# Street_Fighter_v1_2.net
KiCad netlist of a schematic drawn in EAGLE
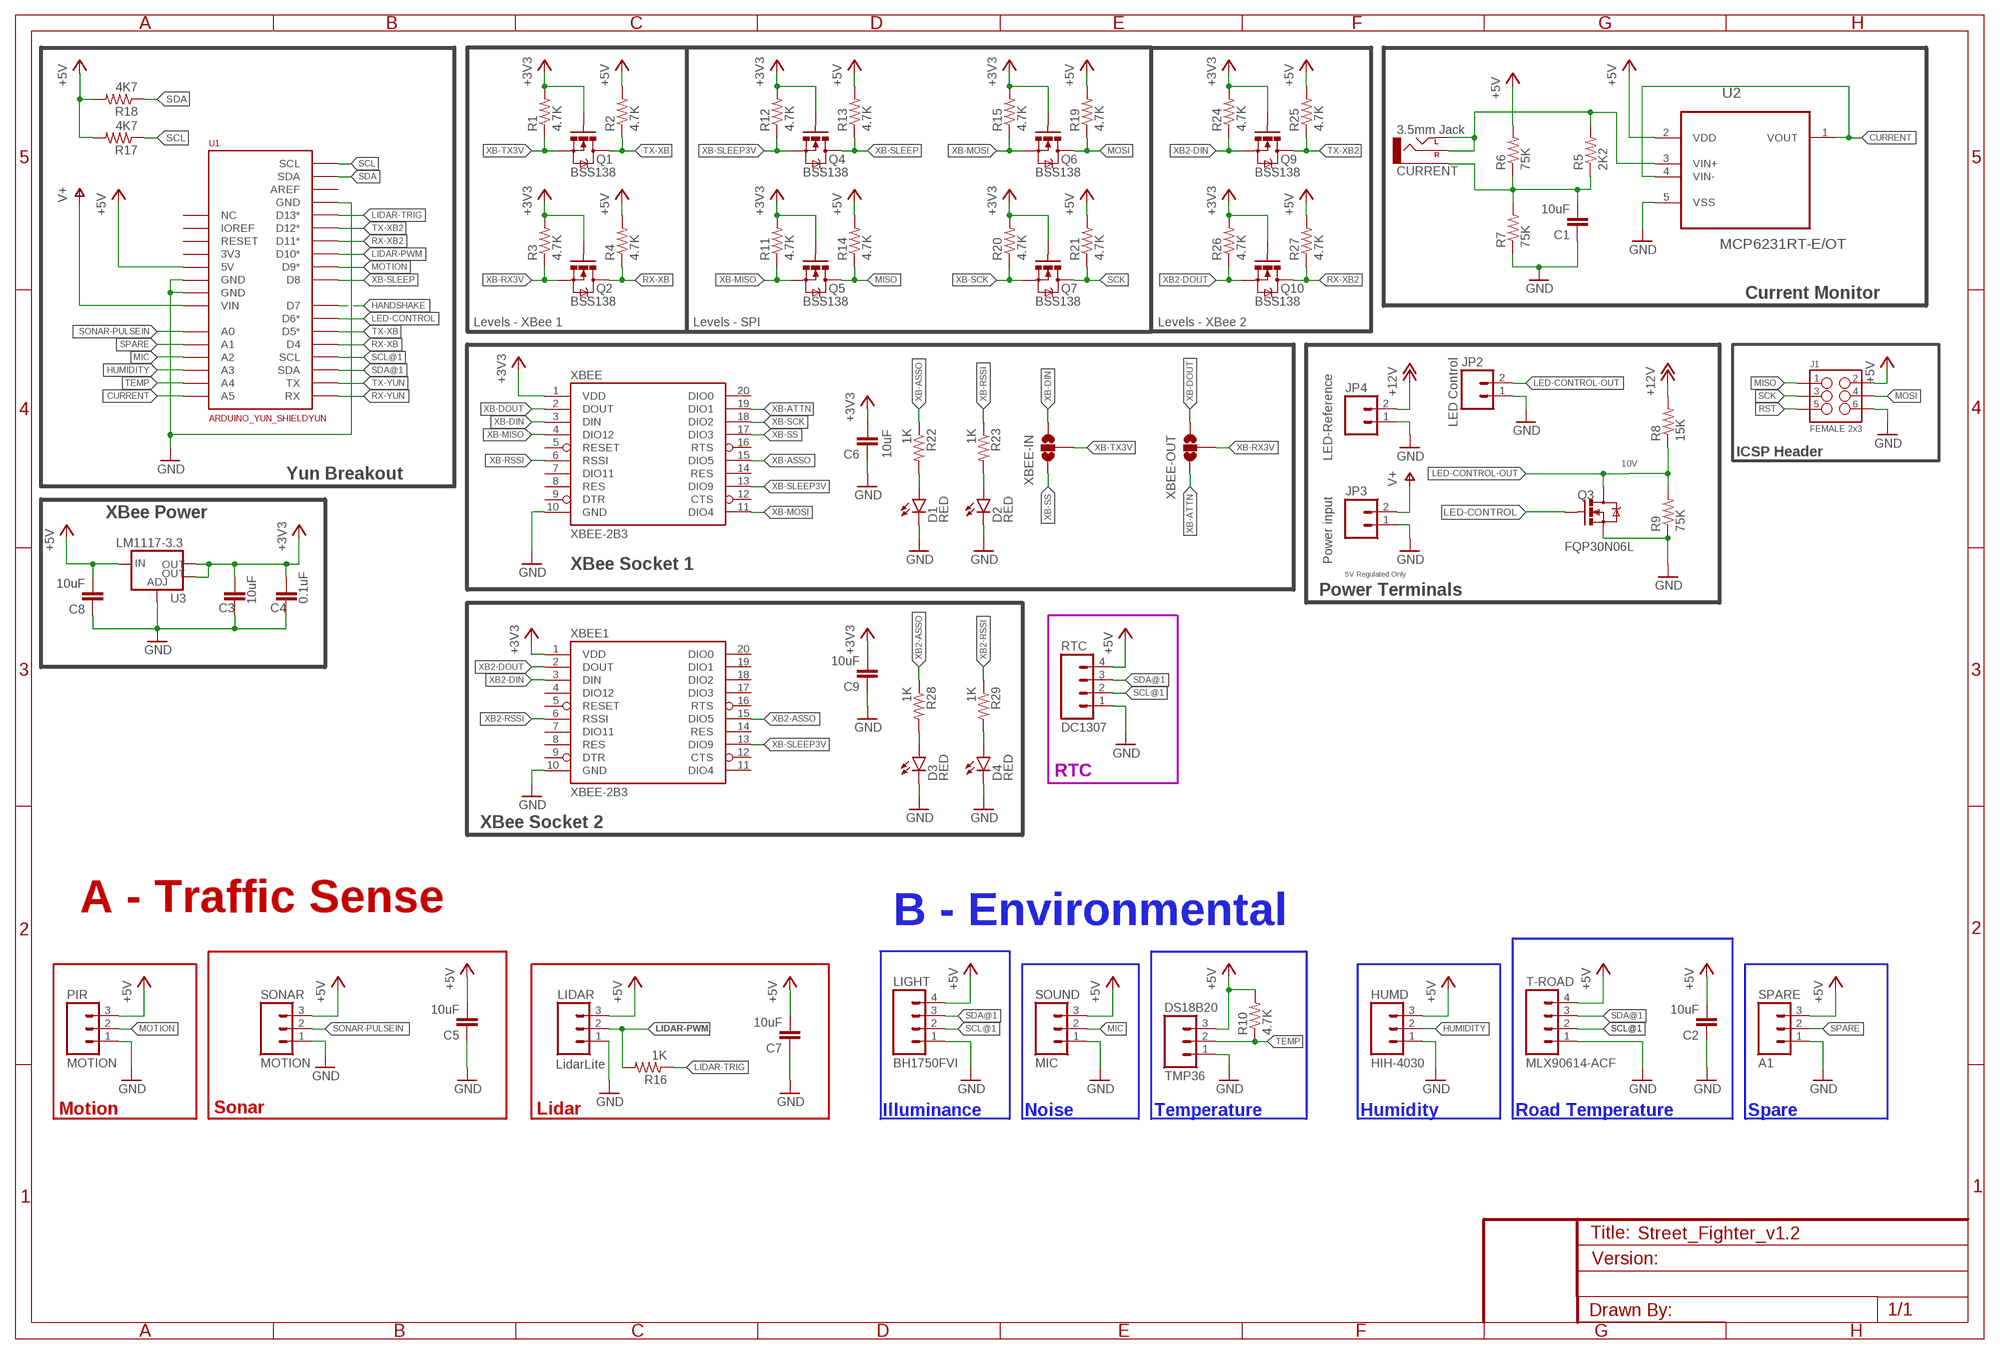
[diagram p0: schematic, sheet 1]

(export (version "E")
  (design (tool "Eeschema 10.0.6"))
  (components
    (comp (ref "C1")
      (value "10uF")
      (footprint "eagle-import:1206")
      (libsource (lib "eagle-import") (part "10UF-6.3V-20%(1206)"))
    )
    (comp (ref "C2")
      (value "10uF")
      (footprint "eagle-import:1206")
      (libsource (lib "eagle-import") (part "10UF-6.3V-20%(1206)"))
    )
    (comp (ref "C3")
      (value "10uF")
      (footprint "eagle-import:1206")
      (libsource (lib "eagle-import") (part "10UF-6.3V-20%(1206)"))
    )
    (comp (ref "C4")
      (value "0.1uF")
      (footprint "eagle-import:1206")
      (libsource (lib "eagle-import") (part "10UF-6.3V-20%(1206)"))
    )
    (comp (ref "C5")
      (value "10uF")
      (footprint "eagle-import:1206")
      (libsource (lib "eagle-import") (part "10UF-6.3V-20%(1206)"))
    )
    (comp (ref "C6")
      (value "10uF")
      (footprint "eagle-import:1206")
      (libsource (lib "eagle-import") (part "10UF-6.3V-20%(1206)"))
    )
    (comp (ref "C7")
      (value "10uF")
      (footprint "eagle-import:1206")
      (libsource (lib "eagle-import") (part "10UF-6.3V-20%(1206)"))
    )
    (comp (ref "C8")
      (value "10uF")
      (footprint "eagle-import:1206")
      (libsource (lib "eagle-import") (part "10UF-6.3V-20%(1206)"))
    )
    (comp (ref "C9")
      (value "10uF")
      (footprint "eagle-import:1206")
      (libsource (lib "eagle-import") (part "10UF-6.3V-20%(1206)"))
    )
    (comp (ref "CURRENT")
      (value "3.5mm Jack")
      (footprint "eagle-import:AUDIO-JACK")
      (libsource (lib "eagle-import") (part "AUDIO-JACKPTH"))
    )
    (comp (ref "D1")
      (value "RED")
      (footprint "eagle-import:LED-1206")
      (libsource (lib "eagle-import") (part "LED-RED1206"))
    )
    (comp (ref "D2")
      (value "RED")
      (footprint "eagle-import:LED-1206")
      (libsource (lib "eagle-import") (part "LED-RED1206"))
    )
    (comp (ref "D3")
      (value "RED")
      (footprint "eagle-import:LED-1206")
      (libsource (lib "eagle-import") (part "LED-RED1206"))
    )
    (comp (ref "D4")
      (value "RED")
      (footprint "eagle-import:LED-1206")
      (libsource (lib "eagle-import") (part "LED-RED1206"))
    )
    (comp (ref "DS18B20")
      (value "TMP36")
      (footprint "eagle-import:1X03")
      (libsource (lib "eagle-import") (part "M03PTH"))
    )
    (comp (ref "HUMD")
      (value "HIH-4030")
      (footprint "eagle-import:1X03")
      (libsource (lib "eagle-import") (part "M03PTH"))
    )
    (comp (ref "J1")
      (value "FEMALE 2x3")
      (footprint "eagle-import:2X3")
      (libsource (lib "eagle-import") (part "M03X2FEMALE"))
    )
    (comp (ref "JP2")
      (value "LED Control")
      (footprint "eagle-import:1X02_LONGPADS")
      (libsource (lib "eagle-import") (part "M02PTH3"))
    )
    (comp (ref "JP3")
      (value "Power input")
      (footprint "eagle-import:1X02_LONGPADS")
      (libsource (lib "eagle-import") (part "M02PTH3"))
    )
    (comp (ref "JP4")
      (value "LED-Reference")
      (footprint "eagle-import:1X02_LONGPADS")
      (libsource (lib "eagle-import") (part "M02PTH3"))
    )
    (comp (ref "LIDAR")
      (value "LidarLite")
      (footprint "eagle-import:1X03")
      (libsource (lib "eagle-import") (part "M03PTH"))
    )
    (comp (ref "LIGHT")
      (value "BH1750FVI")
      (footprint "eagle-import:1X04")
      (libsource (lib "eagle-import") (part "M04PTH"))
    )
    (comp (ref "PIR")
      (value "MOTION")
      (footprint "eagle-import:1X03")
      (libsource (lib "eagle-import") (part "M03PTH"))
    )
    (comp (ref "Q1")
      (value "BSS138")
      (footprint "eagle-import:SOT23")
      (libsource (lib "eagle-import") (part "MOSFET-NCHANNELBSS123LT1G"))
    )
    (comp (ref "Q2")
      (value "BSS138")
      (footprint "eagle-import:SOT23")
      (libsource (lib "eagle-import") (part "MOSFET-NCHANNELBSS123LT1G"))
    )
    (comp (ref "Q3")
      (value "FQP30N06L")
      (footprint "eagle-import:TO220V")
      (libsource (lib "eagle-import") (part "MOSFET-NCHANNELFQP30N06L"))
    )
    (comp (ref "Q4")
      (value "BSS138")
      (footprint "eagle-import:SOT23")
      (libsource (lib "eagle-import") (part "MOSFET-NCHANNELBSS123LT1G"))
    )
    (comp (ref "Q5")
      (value "BSS138")
      (footprint "eagle-import:SOT23")
      (libsource (lib "eagle-import") (part "MOSFET-NCHANNELBSS123LT1G"))
    )
    (comp (ref "Q6")
      (value "BSS138")
      (footprint "eagle-import:SOT23")
      (libsource (lib "eagle-import") (part "MOSFET-NCHANNELBSS123LT1G"))
    )
    (comp (ref "Q7")
      (value "BSS138")
      (footprint "eagle-import:SOT23")
      (libsource (lib "eagle-import") (part "MOSFET-NCHANNELBSS123LT1G"))
    )
    (comp (ref "Q9")
      (value "BSS138")
      (footprint "eagle-import:SOT23")
      (libsource (lib "eagle-import") (part "MOSFET-NCHANNELBSS123LT1G"))
    )
    (comp (ref "Q10")
      (value "BSS138")
      (footprint "eagle-import:SOT23")
      (libsource (lib "eagle-import") (part "MOSFET-NCHANNELBSS123LT1G"))
    )
    (comp (ref "R1")
      (value "4.7K")
      (footprint "eagle-import:1206")
      (libsource (lib "eagle-import") (part "RESISTOR1206"))
    )
    (comp (ref "R2")
      (value "4.7K")
      (footprint "eagle-import:1206")
      (libsource (lib "eagle-import") (part "RESISTOR1206"))
    )
    (comp (ref "R3")
      (value "4.7K")
      (footprint "eagle-import:1206")
      (libsource (lib "eagle-import") (part "RESISTOR1206"))
    )
    (comp (ref "R4")
      (value "4.7K")
      (footprint "eagle-import:1206")
      (libsource (lib "eagle-import") (part "RESISTOR1206"))
    )
    (comp (ref "R5")
      (value "2K2")
      (footprint "eagle-import:1206")
      (libsource (lib "eagle-import") (part "RESISTOR1206"))
    )
    (comp (ref "R6")
      (value "75K")
      (footprint "eagle-import:1206")
      (libsource (lib "eagle-import") (part "RESISTOR1206"))
    )
    (comp (ref "R7")
      (value "75K")
      (footprint "eagle-import:1206")
      (libsource (lib "eagle-import") (part "RESISTOR1206"))
    )
    (comp (ref "R8")
      (value "15K")
      (footprint "eagle-import:1206")
      (libsource (lib "eagle-import") (part "RESISTOR1206"))
    )
    (comp (ref "R9")
      (value "75K")
      (footprint "eagle-import:1206")
      (libsource (lib "eagle-import") (part "RESISTOR1206"))
    )
    (comp (ref "R10")
      (value "4.7K")
      (footprint "eagle-import:1206")
      (libsource (lib "eagle-import") (part "RESISTOR1206"))
    )
    (comp (ref "R11")
      (value "4.7K")
      (footprint "eagle-import:1206")
      (libsource (lib "eagle-import") (part "RESISTOR1206"))
    )
    (comp (ref "R12")
      (value "4.7K")
      (footprint "eagle-import:1206")
      (libsource (lib "eagle-import") (part "RESISTOR1206"))
    )
    (comp (ref "R13")
      (value "4.7K")
      (footprint "eagle-import:1206")
      (libsource (lib "eagle-import") (part "RESISTOR1206"))
    )
    (comp (ref "R14")
      (value "4.7K")
      (footprint "eagle-import:1206")
      (libsource (lib "eagle-import") (part "RESISTOR1206"))
    )
    (comp (ref "R15")
      (value "4.7K")
      (footprint "eagle-import:1206")
      (libsource (lib "eagle-import") (part "RESISTOR1206"))
    )
    (comp (ref "R16")
      (value "1K")
      (footprint "eagle-import:1206")
      (libsource (lib "eagle-import") (part "RESISTOR1206"))
    )
    (comp (ref "R17")
      (value "4K7")
      (footprint "eagle-import:1206")
      (libsource (lib "eagle-import") (part "RESISTOR1206"))
    )
    (comp (ref "R18")
      (value "4K7")
      (footprint "eagle-import:1206")
      (libsource (lib "eagle-import") (part "RESISTOR1206"))
    )
    (comp (ref "R19")
      (value "4.7K")
      (footprint "eagle-import:1206")
      (libsource (lib "eagle-import") (part "RESISTOR1206"))
    )
    (comp (ref "R20")
      (value "4.7K")
      (footprint "eagle-import:1206")
      (libsource (lib "eagle-import") (part "RESISTOR1206"))
    )
    (comp (ref "R21")
      (value "4.7K")
      (footprint "eagle-import:1206")
      (libsource (lib "eagle-import") (part "RESISTOR1206"))
    )
    (comp (ref "R22")
      (value "1K")
      (footprint "eagle-import:1206")
      (libsource (lib "eagle-import") (part "RESISTOR1206"))
    )
    (comp (ref "R23")
      (value "1K")
      (footprint "eagle-import:1206")
      (libsource (lib "eagle-import") (part "RESISTOR1206"))
    )
    (comp (ref "R24")
      (value "4.7K")
      (footprint "eagle-import:1206")
      (libsource (lib "eagle-import") (part "RESISTOR1206"))
    )
    (comp (ref "R25")
      (value "4.7K")
      (footprint "eagle-import:1206")
      (libsource (lib "eagle-import") (part "RESISTOR1206"))
    )
    (comp (ref "R26")
      (value "4.7K")
      (footprint "eagle-import:1206")
      (libsource (lib "eagle-import") (part "RESISTOR1206"))
    )
    (comp (ref "R27")
      (value "4.7K")
      (footprint "eagle-import:1206")
      (libsource (lib "eagle-import") (part "RESISTOR1206"))
    )
    (comp (ref "R28")
      (value "1K")
      (footprint "eagle-import:1206")
      (libsource (lib "eagle-import") (part "RESISTOR1206"))
    )
    (comp (ref "R29")
      (value "1K")
      (footprint "eagle-import:1206")
      (libsource (lib "eagle-import") (part "RESISTOR1206"))
    )
    (comp (ref "RTC")
      (value "DC1307")
      (footprint "eagle-import:1X04")
      (libsource (lib "eagle-import") (part "M04PTH"))
    )
    (comp (ref "SONAR")
      (value "MOTION")
      (footprint "eagle-import:1X03")
      (libsource (lib "eagle-import") (part "M03PTH"))
    )
    (comp (ref "SOUND")
      (value "MIC")
      (footprint "eagle-import:1X03")
      (libsource (lib "eagle-import") (part "M03PTH"))
    )
    (comp (ref "SPARE")
      (value "A1")
      (footprint "eagle-import:1X03")
      (libsource (lib "eagle-import") (part "M03PTH"))
    )
    (comp (ref "T-ROAD")
      (value "MLX90614-ACF")
      (footprint "eagle-import:1X04")
      (libsource (lib "eagle-import") (part "M04PTH"))
    )
    (comp (ref "U1")
      (value "ARDUINO_YUN_SHIELDYUN")
      (footprint "eagle-import:DUEMILANOVE_VIAS")
      (libsource (lib "eagle-import") (part "ARDUINO_YUN_SHIELDYUN"))
    )
    (comp (ref "U2")
      (value "MCP6231RT-E/OT")
      (footprint "eagle-import:SOT95P270X145-5N")
      (libsource (lib "eagle-import") (part "MCP6231RT-E/OT"))
    )
    (comp (ref "U3")
      (value "LM1117-3.3")
      (footprint "eagle-import:SOT223")
      (libsource (lib "eagle-import") (part "V_REG_LM1117SOT223"))
    )
    (comp (ref "XBEE")
      (value "XBEE-2B3")
      (footprint "eagle-import:XBEE-SMD")
      (libsource (lib "eagle-import") (part "XBEE-2B3"))
    )
    (comp (ref "XBEE-IN")
      (value "SOLDERJUMPER_2WAYS")
      (footprint "eagle-import:SJ_3")
      (libsource (lib "eagle-import") (part "SOLDERJUMPER_2WAYS"))
    )
    (comp (ref "XBEE-OUT")
      (value "SOLDERJUMPER_2WAYS")
      (footprint "eagle-import:SJ_3")
      (libsource (lib "eagle-import") (part "SOLDERJUMPER_2WAYS"))
    )
    (comp (ref "XBEE1")
      (value "XBEE-2B3")
      (footprint "eagle-import:XBEE-SMD")
      (libsource (lib "eagle-import") (part "XBEE-2B3"))
    )
  )
  (nets
    (net (code "1") (name "+3V3") (class "Default")
      (node (ref "C3") (pin "2") (pinfunction "2_2") (pintype "passive"))
      (node (ref "C4") (pin "2") (pinfunction "2_2") (pintype "passive"))
      (node (ref "C6") (pin "2") (pinfunction "2_2") (pintype "passive"))
      (node (ref "C9") (pin "2") (pinfunction "2_2") (pintype "passive"))
      (node (ref "Q1") (pin "1") (pinfunction "G_1") (pintype "passive"))
      (node (ref "Q10") (pin "1") (pinfunction "G_1") (pintype "passive"))
      (node (ref "Q2") (pin "1") (pinfunction "G_1") (pintype "passive"))
      (node (ref "Q4") (pin "1") (pinfunction "G_1") (pintype "passive"))
      (node (ref "Q5") (pin "1") (pinfunction "G_1") (pintype "passive"))
      (node (ref "Q6") (pin "1") (pinfunction "G_1") (pintype "passive"))
      (node (ref "Q7") (pin "1") (pinfunction "G_1") (pintype "passive"))
      (node (ref "Q9") (pin "1") (pinfunction "G_1") (pintype "passive"))
      (node (ref "R1") (pin "2") (pinfunction "2_2") (pintype "passive"))
      (node (ref "R11") (pin "2") (pinfunction "2_2") (pintype "passive"))
      (node (ref "R12") (pin "2") (pinfunction "2_2") (pintype "passive"))
      (node (ref "R15") (pin "2") (pinfunction "2_2") (pintype "passive"))
      (node (ref "R20") (pin "2") (pinfunction "2_2") (pintype "passive"))
      (node (ref "R24") (pin "2") (pinfunction "2_2") (pintype "passive"))
      (node (ref "R26") (pin "2") (pinfunction "2_2") (pintype "passive"))
      (node (ref "R3") (pin "2") (pinfunction "2_2") (pintype "passive"))
      (node (ref "U3") (pin "2") (pinfunction "OUT_2") (pintype "output"))
      (node (ref "U3") (pin "4") (pinfunction "OUT_4") (pintype "output"))
      (node (ref "XBEE") (pin "1") (pinfunction "VDD_1") (pintype "power_in"))
      (node (ref "XBEE1") (pin "1") (pinfunction "VDD_1") (pintype "power_in"))
    )
    (net (code "2") (name "+5V") (class "Default")
      (node (ref "C2") (pin "2") (pinfunction "2_2") (pintype "passive"))
      (node (ref "C5") (pin "2") (pinfunction "2_2") (pintype "passive"))
      (node (ref "C7") (pin "2") (pinfunction "2_2") (pintype "passive"))
      (node (ref "C8") (pin "2") (pinfunction "2_2") (pintype "passive"))
      (node (ref "DS18B20") (pin "3") (pinfunction "3_3") (pintype "passive"))
      (node (ref "HUMD") (pin "3") (pinfunction "3_3") (pintype "passive"))
      (node (ref "J1") (pin "2") (pinfunction "2_2") (pintype "bidirectional"))
      (node (ref "LIDAR") (pin "3") (pinfunction "3_3") (pintype "passive"))
      (node (ref "LIGHT") (pin "4") (pinfunction "4_4") (pintype "passive"))
      (node (ref "PIR") (pin "3") (pinfunction "3_3") (pintype "passive"))
      (node (ref "R10") (pin "2") (pinfunction "2_2") (pintype "passive"))
      (node (ref "R13") (pin "2") (pinfunction "2_2") (pintype "passive"))
      (node (ref "R14") (pin "2") (pinfunction "2_2") (pintype "passive"))
      (node (ref "R17") (pin "2") (pinfunction "2_2") (pintype "passive"))
      (node (ref "R18") (pin "2") (pinfunction "2_2") (pintype "passive"))
      (node (ref "R19") (pin "2") (pinfunction "2_2") (pintype "passive"))
      (node (ref "R2") (pin "2") (pinfunction "2_2") (pintype "passive"))
      (node (ref "R21") (pin "2") (pinfunction "2_2") (pintype "passive"))
      (node (ref "R25") (pin "2") (pinfunction "2_2") (pintype "passive"))
      (node (ref "R27") (pin "2") (pinfunction "2_2") (pintype "passive"))
      (node (ref "R4") (pin "2") (pinfunction "2_2") (pintype "passive"))
      (node (ref "R6") (pin "2") (pinfunction "2_2") (pintype "passive"))
      (node (ref "RTC") (pin "4") (pinfunction "4_4") (pintype "passive"))
      (node (ref "SONAR") (pin "3") (pinfunction "3_3") (pintype "passive"))
      (node (ref "SOUND") (pin "3") (pinfunction "3_3") (pintype "passive"))
      (node (ref "SPARE") (pin "3") (pinfunction "3_3") (pintype "passive"))
      (node (ref "T-ROAD") (pin "4") (pinfunction "4_4") (pintype "passive"))
      (node (ref "U1") (pin "5V") (pinfunction "5V_5V") (pintype "power_in"))
      (node (ref "U2") (pin "2") (pinfunction "VDD_2") (pintype "power_in"))
      (node (ref "U3") (pin "3") (pinfunction "IN_3") (pintype "input"))
    )
    (net (code "3") (name "+12V") (class "Default")
      (node (ref "JP4") (pin "2") (pinfunction "2_2") (pintype "passive"))
      (node (ref "R8") (pin "2") (pinfunction "2_2") (pintype "passive"))
    )
    (net (code "4") (name "/3V3") (class "Default")
      (node (ref "U1") (pin "3V3") (pinfunction "3V3_3V3") (pintype "power_in"))
    )
    (net (code "5") (name "CURRENT") (class "Default")
      (node (ref "U1") (pin "A5") (pinfunction "A5_A5") (pintype "bidirectional"))
      (node (ref "U2") (pin "1") (pinfunction "VOUT_1") (pintype "output"))
      (node (ref "U2") (pin "4") (pinfunction "VIN-_4") (pintype "input"))
    )
    (net (code "6") (name "GND") (class "Default")
      (node (ref "C1") (pin "1") (pinfunction "1_1") (pintype "passive"))
      (node (ref "C2") (pin "1") (pinfunction "1_1") (pintype "passive"))
      (node (ref "C3") (pin "1") (pinfunction "1_1") (pintype "passive"))
      (node (ref "C4") (pin "1") (pinfunction "1_1") (pintype "passive"))
      (node (ref "C5") (pin "1") (pinfunction "1_1") (pintype "passive"))
      (node (ref "C6") (pin "1") (pinfunction "1_1") (pintype "passive"))
      (node (ref "C7") (pin "1") (pinfunction "1_1") (pintype "passive"))
      (node (ref "C8") (pin "1") (pinfunction "1_1") (pintype "passive"))
      (node (ref "C9") (pin "1") (pinfunction "1_1") (pintype "passive"))
      (node (ref "D1") (pin "C") (pinfunction "C_C") (pintype "passive"))
      (node (ref "D2") (pin "C") (pinfunction "C_C") (pintype "passive"))
      (node (ref "D3") (pin "C") (pinfunction "C_C") (pintype "passive"))
      (node (ref "D4") (pin "C") (pinfunction "C_C") (pintype "passive"))
      (node (ref "DS18B20") (pin "1") (pinfunction "1_1") (pintype "passive"))
      (node (ref "HUMD") (pin "1") (pinfunction "1_1") (pintype "passive"))
      (node (ref "J1") (pin "6") (pinfunction "6_6") (pintype "bidirectional"))
      (node (ref "JP2") (pin "1") (pinfunction "1_1") (pintype "passive"))
      (node (ref "JP3") (pin "1") (pinfunction "1_1") (pintype "passive"))
      (node (ref "JP4") (pin "1") (pinfunction "1_1") (pintype "passive"))
      (node (ref "LIDAR") (pin "1") (pinfunction "1_1") (pintype "passive"))
      (node (ref "LIGHT") (pin "1") (pinfunction "1_1") (pintype "passive"))
      (node (ref "PIR") (pin "1") (pinfunction "1_1") (pintype "passive"))
      (node (ref "Q3") (pin "3") (pinfunction "S_3") (pintype "passive"))
      (node (ref "R7") (pin "1") (pinfunction "1_1") (pintype "passive"))
      (node (ref "R9") (pin "1") (pinfunction "1_1") (pintype "passive"))
      (node (ref "RTC") (pin "1") (pinfunction "1_1") (pintype "passive"))
      (node (ref "SONAR") (pin "1") (pinfunction "1_1") (pintype "passive"))
      (node (ref "SOUND") (pin "1") (pinfunction "1_1") (pintype "passive"))
      (node (ref "SPARE") (pin "1") (pinfunction "1_1") (pintype "passive"))
      (node (ref "T-ROAD") (pin "1") (pinfunction "1_1") (pintype "passive"))
      (node (ref "U1") (pin "GND") (pinfunction "GND_GND") (pintype "power_in"))
      (node (ref "U1") (pin "GND@0") (pinfunction "GND_GND@0") (pintype "power_in"))
      (node (ref "U1") (pin "GND@1") (pinfunction "GND_GND@1") (pintype "power_in"))
      (node (ref "U2") (pin "5") (pinfunction "VSS_5") (pintype "passive"))
      (node (ref "U3") (pin "1") (pinfunction "ADJ_1") (pintype "input"))
      (node (ref "XBEE") (pin "10") (pinfunction "GND_10") (pintype "power_in"))
      (node (ref "XBEE1") (pin "10") (pinfunction "GND_10") (pintype "power_in"))
    )
    (net (code "7") (name "HANDSHAKE") (class "Default")
      (node (ref "U1") (pin "7") (pinfunction "D7_7") (pintype "bidirectional"))
    )
    (net (code "8") (name "HUMIDITY") (class "Default")
      (node (ref "HUMD") (pin "2") (pinfunction "2_2") (pintype "passive"))
      (node (ref "U1") (pin "A3") (pinfunction "A3_A3") (pintype "bidirectional"))
    )
    (net (code "9") (name "LED-CONTROL") (class "Default")
      (node (ref "Q3") (pin "1") (pinfunction "G_1") (pintype "passive"))
      (node (ref "U1") (pin "6") (pinfunction "D6*_6") (pintype "bidirectional"))
    )
    (net (code "10") (name "LED-CONTROL-OUT") (class "Default")
      (node (ref "JP2") (pin "2") (pinfunction "2_2") (pintype "passive"))
      (node (ref "Q3") (pin "2") (pinfunction "D_2") (pintype "passive"))
      (node (ref "R8") (pin "1") (pinfunction "1_1") (pintype "passive"))
      (node (ref "R9") (pin "2") (pinfunction "2_2") (pintype "passive"))
    )
    (net (code "11") (name "LIDAR-PWM") (class "Default")
      (node (ref "LIDAR") (pin "2") (pinfunction "2_2") (pintype "passive"))
      (node (ref "R16") (pin "2") (pinfunction "2_2") (pintype "passive"))
      (node (ref "U1") (pin "10") (pinfunction "D10*_10") (pintype "bidirectional"))
    )
    (net (code "12") (name "LIDAR-TRIG") (class "Default")
      (node (ref "R16") (pin "1") (pinfunction "1_1") (pintype "passive"))
      (node (ref "U1") (pin "13") (pinfunction "D13*_13") (pintype "bidirectional"))
    )
    (net (code "13") (name "MIC") (class "Default")
      (node (ref "SOUND") (pin "2") (pinfunction "2_2") (pintype "passive"))
      (node (ref "U1") (pin "A2") (pinfunction "A2_A2") (pintype "bidirectional"))
    )
    (net (code "14") (name "MISO") (class "Default")
      (node (ref "J1") (pin "1") (pinfunction "1_1") (pintype "bidirectional"))
      (node (ref "Q5") (pin "3") (pinfunction "D_3") (pintype "passive"))
      (node (ref "R14") (pin "1") (pinfunction "1_1") (pintype "passive"))
    )
    (net (code "15") (name "MOSI") (class "Default")
      (node (ref "J1") (pin "4") (pinfunction "4_4") (pintype "bidirectional"))
      (node (ref "Q6") (pin "3") (pinfunction "D_3") (pintype "passive"))
      (node (ref "R19") (pin "1") (pinfunction "1_1") (pintype "passive"))
    )
    (net (code "16") (name "MOTION") (class "Default")
      (node (ref "PIR") (pin "2") (pinfunction "2_2") (pintype "passive"))
      (node (ref "U1") (pin "9") (pinfunction "D9*_9") (pintype "bidirectional"))
    )
    (net (code "17") (name "Net-(C1-Pad2)") (class "Default")
      (node (ref "C1") (pin "2") (pinfunction "2_2") (pintype "passive"))
      (node (ref "CURRENT") (pin "SLEEVE") (pinfunction "SLEEVE_SLEEVE") (pintype "bidirectional"))
      (node (ref "R5") (pin "1") (pinfunction "1_1") (pintype "passive"))
      (node (ref "R6") (pin "1") (pinfunction "1_1") (pintype "passive"))
      (node (ref "R7") (pin "2") (pinfunction "2_2") (pintype "passive"))
    )
    (net (code "18") (name "Net-(CURRENT-LEFT)") (class "Default")
      (node (ref "CURRENT") (pin "RING") (pinfunction "RIGHT_RING") (pintype "bidirectional"))
      (node (ref "CURRENT") (pin "TIP") (pinfunction "LEFT_TIP") (pintype "bidirectional"))
      (node (ref "R5") (pin "2") (pinfunction "2_2") (pintype "passive"))
      (node (ref "U2") (pin "3") (pinfunction "VIN+_3") (pintype "input"))
    )
    (net (code "19") (name "Net-(D1-PadA)") (class "Default")
      (node (ref "D1") (pin "A") (pinfunction "A_A") (pintype "passive"))
      (node (ref "R22") (pin "2") (pinfunction "2_2") (pintype "passive"))
    )
    (net (code "20") (name "Net-(D2-PadA)") (class "Default")
      (node (ref "D2") (pin "A") (pinfunction "A_A") (pintype "passive"))
      (node (ref "R23") (pin "2") (pinfunction "2_2") (pintype "passive"))
    )
    (net (code "21") (name "Net-(D3-PadA)") (class "Default")
      (node (ref "D3") (pin "A") (pinfunction "A_A") (pintype "passive"))
      (node (ref "R28") (pin "2") (pinfunction "2_2") (pintype "passive"))
    )
    (net (code "22") (name "Net-(D4-PadA)") (class "Default")
      (node (ref "D4") (pin "A") (pinfunction "A_A") (pintype "passive"))
      (node (ref "R29") (pin "2") (pinfunction "2_2") (pintype "passive"))
    )
    (net (code "23") (name "RST") (class "Default")
      (node (ref "J1") (pin "5") (pinfunction "5_5") (pintype "bidirectional"))
    )
    (net (code "24") (name "RX-XB") (class "Default")
      (node (ref "Q2") (pin "3") (pinfunction "D_3") (pintype "passive"))
      (node (ref "R4") (pin "1") (pinfunction "1_1") (pintype "passive"))
      (node (ref "U1") (pin "D4") (pinfunction "D4_D4") (pintype "bidirectional"))
    )
    (net (code "25") (name "RX-XB2") (class "Default")
      (node (ref "Q10") (pin "3") (pinfunction "D_3") (pintype "passive"))
      (node (ref "R27") (pin "1") (pinfunction "1_1") (pintype "passive"))
      (node (ref "U1") (pin "11") (pinfunction "D11*_11") (pintype "bidirectional"))
    )
    (net (code "26") (name "RX-YUN") (class "Default")
      (node (ref "U1") (pin "0") (pinfunction "RX_0") (pintype "bidirectional"))
    )
    (net (code "27") (name "SCK") (class "Default")
      (node (ref "J1") (pin "3") (pinfunction "3_3") (pintype "bidirectional"))
      (node (ref "Q7") (pin "3") (pinfunction "D_3") (pintype "passive"))
      (node (ref "R21") (pin "1") (pinfunction "1_1") (pintype "passive"))
    )
    (net (code "28") (name "SCL") (class "Default")
      (node (ref "R17") (pin "1") (pinfunction "1_1") (pintype "passive"))
      (node (ref "U1") (pin "3@1") (pinfunction "SCL_3@1") (pintype "bidirectional"))
    )
    (net (code "29") (name "SCL@1") (class "Default")
      (node (ref "LIGHT") (pin "2") (pinfunction "2_2") (pintype "passive"))
      (node (ref "RTC") (pin "2") (pinfunction "2_2") (pintype "passive"))
      (node (ref "T-ROAD") (pin "2") (pinfunction "2_2") (pintype "passive"))
      (node (ref "U1") (pin "3") (pinfunction "SCL_3") (pintype "bidirectional"))
    )
    (net (code "30") (name "SDA") (class "Default")
      (node (ref "R18") (pin "1") (pinfunction "1_1") (pintype "passive"))
      (node (ref "U1") (pin "2@1") (pinfunction "SDA_2@1") (pintype "bidirectional"))
    )
    (net (code "31") (name "SDA@1") (class "Default")
      (node (ref "LIGHT") (pin "3") (pinfunction "3_3") (pintype "passive"))
      (node (ref "RTC") (pin "3") (pinfunction "3_3") (pintype "passive"))
      (node (ref "T-ROAD") (pin "3") (pinfunction "3_3") (pintype "passive"))
      (node (ref "U1") (pin "2") (pinfunction "SDA_2") (pintype "bidirectional"))
    )
    (net (code "32") (name "SONAR-PULSEIN") (class "Default")
      (node (ref "SONAR") (pin "2") (pinfunction "2_2") (pintype "passive"))
      (node (ref "U1") (pin "A0") (pinfunction "A0_A0") (pintype "bidirectional"))
    )
    (net (code "33") (name "SPARE") (class "Default")
      (node (ref "SPARE") (pin "2") (pinfunction "2_2") (pintype "passive"))
      (node (ref "U1") (pin "A1") (pinfunction "A1_A1") (pintype "bidirectional"))
    )
    (net (code "34") (name "TEMP") (class "Default")
      (node (ref "DS18B20") (pin "2") (pinfunction "2_2") (pintype "passive"))
      (node (ref "R10") (pin "1") (pinfunction "1_1") (pintype "passive"))
      (node (ref "U1") (pin "A4") (pinfunction "A4_A4") (pintype "bidirectional"))
    )
    (net (code "35") (name "TX-XB") (class "Default")
      (node (ref "Q1") (pin "3") (pinfunction "D_3") (pintype "passive"))
      (node (ref "R2") (pin "1") (pinfunction "1_1") (pintype "passive"))
      (node (ref "U1") (pin "5") (pinfunction "D5*_5") (pintype "bidirectional"))
    )
    (net (code "36") (name "TX-XB2") (class "Default")
      (node (ref "Q9") (pin "3") (pinfunction "D_3") (pintype "passive"))
      (node (ref "R25") (pin "1") (pinfunction "1_1") (pintype "passive"))
      (node (ref "U1") (pin "12") (pinfunction "D12*_12") (pintype "bidirectional"))
    )
    (net (code "37") (name "TX-YUN") (class "Default")
      (node (ref "U1") (pin "1") (pinfunction "TX_1") (pintype "bidirectional"))
    )
    (net (code "38") (name "V+") (class "Default")
      (node (ref "JP3") (pin "2") (pinfunction "2_2") (pintype "passive"))
      (node (ref "U1") (pin "VIN") (pinfunction "VIN_VIN") (pintype "power_in"))
    )
    (net (code "39") (name "XB-ASSO") (class "Default")
      (node (ref "R22") (pin "1") (pinfunction "1_1") (pintype "passive"))
      (node (ref "XBEE") (pin "15") (pinfunction "DIO5_15") (pintype "bidirectional"))
    )
    (net (code "40") (name "XB-ATTN") (class "Default")
      (node (ref "XBEE") (pin "19") (pinfunction "DIO1_19") (pintype "bidirectional"))
      (node (ref "XBEE-OUT") (pin "1") (pinfunction "1_1") (pintype "passive"))
    )
    (net (code "41") (name "XB-DIN") (class "Default")
      (node (ref "XBEE") (pin "3") (pinfunction "DIN_3") (pintype "input"))
      (node (ref "XBEE-IN") (pin "3") (pinfunction "3_3") (pintype "passive"))
    )
    (net (code "42") (name "XB-DOUT") (class "Default")
      (node (ref "XBEE") (pin "2") (pinfunction "DOUT_2") (pintype "output"))
      (node (ref "XBEE-OUT") (pin "3") (pinfunction "3_3") (pintype "passive"))
    )
    (net (code "43") (name "XB-MISO") (class "Default")
      (node (ref "Q5") (pin "2") (pinfunction "S_2") (pintype "passive"))
      (node (ref "R11") (pin "1") (pinfunction "1_1") (pintype "passive"))
      (node (ref "XBEE") (pin "4") (pinfunction "DIO12_4") (pintype "bidirectional"))
    )
    (net (code "44") (name "XB-MOSI") (class "Default")
      (node (ref "Q6") (pin "2") (pinfunction "S_2") (pintype "passive"))
      (node (ref "R15") (pin "1") (pinfunction "1_1") (pintype "passive"))
      (node (ref "XBEE") (pin "11") (pinfunction "DIO4_11") (pintype "bidirectional"))
    )
    (net (code "45") (name "XB-RSSI") (class "Default")
      (node (ref "R23") (pin "1") (pinfunction "1_1") (pintype "passive"))
      (node (ref "XBEE") (pin "6") (pinfunction "RSSI_6") (pintype "bidirectional"))
    )
    (net (code "46") (name "XB-RX3V") (class "Default")
      (node (ref "Q2") (pin "2") (pinfunction "S_2") (pintype "passive"))
      (node (ref "R3") (pin "1") (pinfunction "1_1") (pintype "passive"))
      (node (ref "XBEE-OUT") (pin "2") (pinfunction "2_2") (pintype "passive"))
    )
    (net (code "47") (name "XB-SCK") (class "Default")
      (node (ref "Q7") (pin "2") (pinfunction "S_2") (pintype "passive"))
      (node (ref "R20") (pin "1") (pinfunction "1_1") (pintype "passive"))
      (node (ref "XBEE") (pin "18") (pinfunction "DIO2_18") (pintype "bidirectional"))
    )
    (net (code "48") (name "XB-SLEEP") (class "Default")
      (node (ref "Q4") (pin "3") (pinfunction "D_3") (pintype "passive"))
      (node (ref "R13") (pin "1") (pinfunction "1_1") (pintype "passive"))
      (node (ref "U1") (pin "8") (pinfunction "D8_8") (pintype "bidirectional"))
    )
    (net (code "49") (name "XB-SLEEP3V") (class "Default")
      (node (ref "Q4") (pin "2") (pinfunction "S_2") (pintype "passive"))
      (node (ref "R12") (pin "1") (pinfunction "1_1") (pintype "passive"))
      (node (ref "XBEE") (pin "13") (pinfunction "DIO9_13") (pintype "bidirectional"))
      (node (ref "XBEE1") (pin "13") (pinfunction "DIO9_13") (pintype "bidirectional"))
    )
    (net (code "50") (name "XB-SS") (class "Default")
      (node (ref "XBEE") (pin "17") (pinfunction "DIO3_17") (pintype "bidirectional"))
      (node (ref "XBEE-IN") (pin "1") (pinfunction "1_1") (pintype "passive"))
    )
    (net (code "51") (name "XB-TX3V") (class "Default")
      (node (ref "Q1") (pin "2") (pinfunction "S_2") (pintype "passive"))
      (node (ref "R1") (pin "1") (pinfunction "1_1") (pintype "passive"))
      (node (ref "XBEE-IN") (pin "2") (pinfunction "2_2") (pintype "passive"))
    )
    (net (code "52") (name "XB2-ASSO") (class "Default")
      (node (ref "R28") (pin "1") (pinfunction "1_1") (pintype "passive"))
      (node (ref "XBEE1") (pin "15") (pinfunction "DIO5_15") (pintype "bidirectional"))
    )
    (net (code "53") (name "XB2-DIN") (class "Default")
      (node (ref "Q9") (pin "2") (pinfunction "S_2") (pintype "passive"))
      (node (ref "R24") (pin "1") (pinfunction "1_1") (pintype "passive"))
      (node (ref "XBEE1") (pin "3") (pinfunction "DIN_3") (pintype "input"))
    )
    (net (code "54") (name "XB2-DOUT") (class "Default")
      (node (ref "Q10") (pin "2") (pinfunction "S_2") (pintype "passive"))
      (node (ref "R26") (pin "1") (pinfunction "1_1") (pintype "passive"))
      (node (ref "XBEE1") (pin "2") (pinfunction "DOUT_2") (pintype "output"))
    )
    (net (code "55") (name "XB2-RSSI") (class "Default")
      (node (ref "R29") (pin "1") (pinfunction "1_1") (pintype "passive"))
      (node (ref "XBEE1") (pin "6") (pinfunction "RSSI_6") (pintype "bidirectional"))
    )
    (net (code "56") (name "unconnected-(U1-PadAREF)") (class "Default")
      (node (ref "U1") (pin "AREF") (pinfunction "AREF_AREF") (pintype "bidirectional"))
    )
    (net (code "57") (name "unconnected-(U1-PadIOREF)") (class "Default")
      (node (ref "U1") (pin "IOREF") (pinfunction "IOREF_IOREF") (pintype "bidirectional"))
    )
    (net (code "58") (name "unconnected-(U1-PadNC)") (class "Default")
      (node (ref "U1") (pin "NC") (pinfunction "NC_NC") (pintype "no_connect"))
    )
    (net (code "59") (name "unconnected-(U1-PadRESET)") (class "Default")
      (node (ref "U1") (pin "RESET") (pinfunction "RESET_RESET") (pintype "bidirectional"))
    )
    (net (code "60") (name "unconnected-(XBEE-CTS-Pad12)") (class "Default")
      (node (ref "XBEE") (pin "12") (pinfunction "CTS_12") (pintype "output"))
    )
    (net (code "61") (name "unconnected-(XBEE-DIO0-Pad20)") (class "Default")
      (node (ref "XBEE") (pin "20") (pinfunction "DIO0_20") (pintype "bidirectional"))
    )
    (net (code "62") (name "unconnected-(XBEE-DIO11-Pad7)") (class "Default")
      (node (ref "XBEE") (pin "7") (pinfunction "DIO11_7") (pintype "bidirectional"))
    )
    (net (code "63") (name "unconnected-(XBEE-DTR-Pad9)") (class "Default")
      (node (ref "XBEE") (pin "9") (pinfunction "DTR_9") (pintype "bidirectional"))
    )
    (net (code "64") (name "unconnected-(XBEE-RES-Pad8)") (class "Default")
      (node (ref "XBEE") (pin "8") (pinfunction "RES_8") (pintype "bidirectional"))
    )
    (net (code "65") (name "unconnected-(XBEE-RES-Pad14)") (class "Default")
      (node (ref "XBEE") (pin "14") (pinfunction "RES_14") (pintype "bidirectional"))
    )
    (net (code "66") (name "unconnected-(XBEE-RESET-Pad5)") (class "Default")
      (node (ref "XBEE") (pin "5") (pinfunction "RESET_5") (pintype "input"))
    )
    (net (code "67") (name "unconnected-(XBEE-RTS-Pad16)") (class "Default")
      (node (ref "XBEE") (pin "16") (pinfunction "RTS_16") (pintype "input"))
    )
    (net (code "68") (name "unconnected-(XBEE1-CTS-Pad12)") (class "Default")
      (node (ref "XBEE1") (pin "12") (pinfunction "CTS_12") (pintype "output"))
    )
    (net (code "69") (name "unconnected-(XBEE1-DIO0-Pad20)") (class "Default")
      (node (ref "XBEE1") (pin "20") (pinfunction "DIO0_20") (pintype "bidirectional"))
    )
    (net (code "70") (name "unconnected-(XBEE1-DIO1-Pad19)") (class "Default")
      (node (ref "XBEE1") (pin "19") (pinfunction "DIO1_19") (pintype "bidirectional"))
    )
    (net (code "71") (name "unconnected-(XBEE1-DIO2-Pad18)") (class "Default")
      (node (ref "XBEE1") (pin "18") (pinfunction "DIO2_18") (pintype "bidirectional"))
    )
    (net (code "72") (name "unconnected-(XBEE1-DIO3-Pad17)") (class "Default")
      (node (ref "XBEE1") (pin "17") (pinfunction "DIO3_17") (pintype "bidirectional"))
    )
    (net (code "73") (name "unconnected-(XBEE1-DIO4-Pad11)") (class "Default")
      (node (ref "XBEE1") (pin "11") (pinfunction "DIO4_11") (pintype "bidirectional"))
    )
    (net (code "74") (name "unconnected-(XBEE1-DIO11-Pad7)") (class "Default")
      (node (ref "XBEE1") (pin "7") (pinfunction "DIO11_7") (pintype "bidirectional"))
    )
    (net (code "75") (name "unconnected-(XBEE1-DIO12-Pad4)") (class "Default")
      (node (ref "XBEE1") (pin "4") (pinfunction "DIO12_4") (pintype "bidirectional"))
    )
    (net (code "76") (name "unconnected-(XBEE1-DTR-Pad9)") (class "Default")
      (node (ref "XBEE1") (pin "9") (pinfunction "DTR_9") (pintype "bidirectional"))
    )
    (net (code "77") (name "unconnected-(XBEE1-RES-Pad8)") (class "Default")
      (node (ref "XBEE1") (pin "8") (pinfunction "RES_8") (pintype "bidirectional"))
    )
    (net (code "78") (name "unconnected-(XBEE1-RES-Pad14)") (class "Default")
      (node (ref "XBEE1") (pin "14") (pinfunction "RES_14") (pintype "bidirectional"))
    )
    (net (code "79") (name "unconnected-(XBEE1-RESET-Pad5)") (class "Default")
      (node (ref "XBEE1") (pin "5") (pinfunction "RESET_5") (pintype "input"))
    )
    (net (code "80") (name "unconnected-(XBEE1-RTS-Pad16)") (class "Default")
      (node (ref "XBEE1") (pin "16") (pinfunction "RTS_16") (pintype "input"))
    )
  )
)
